# tc0xC_proto.net
KiCad netlist of a schematic drawn in EAGLE
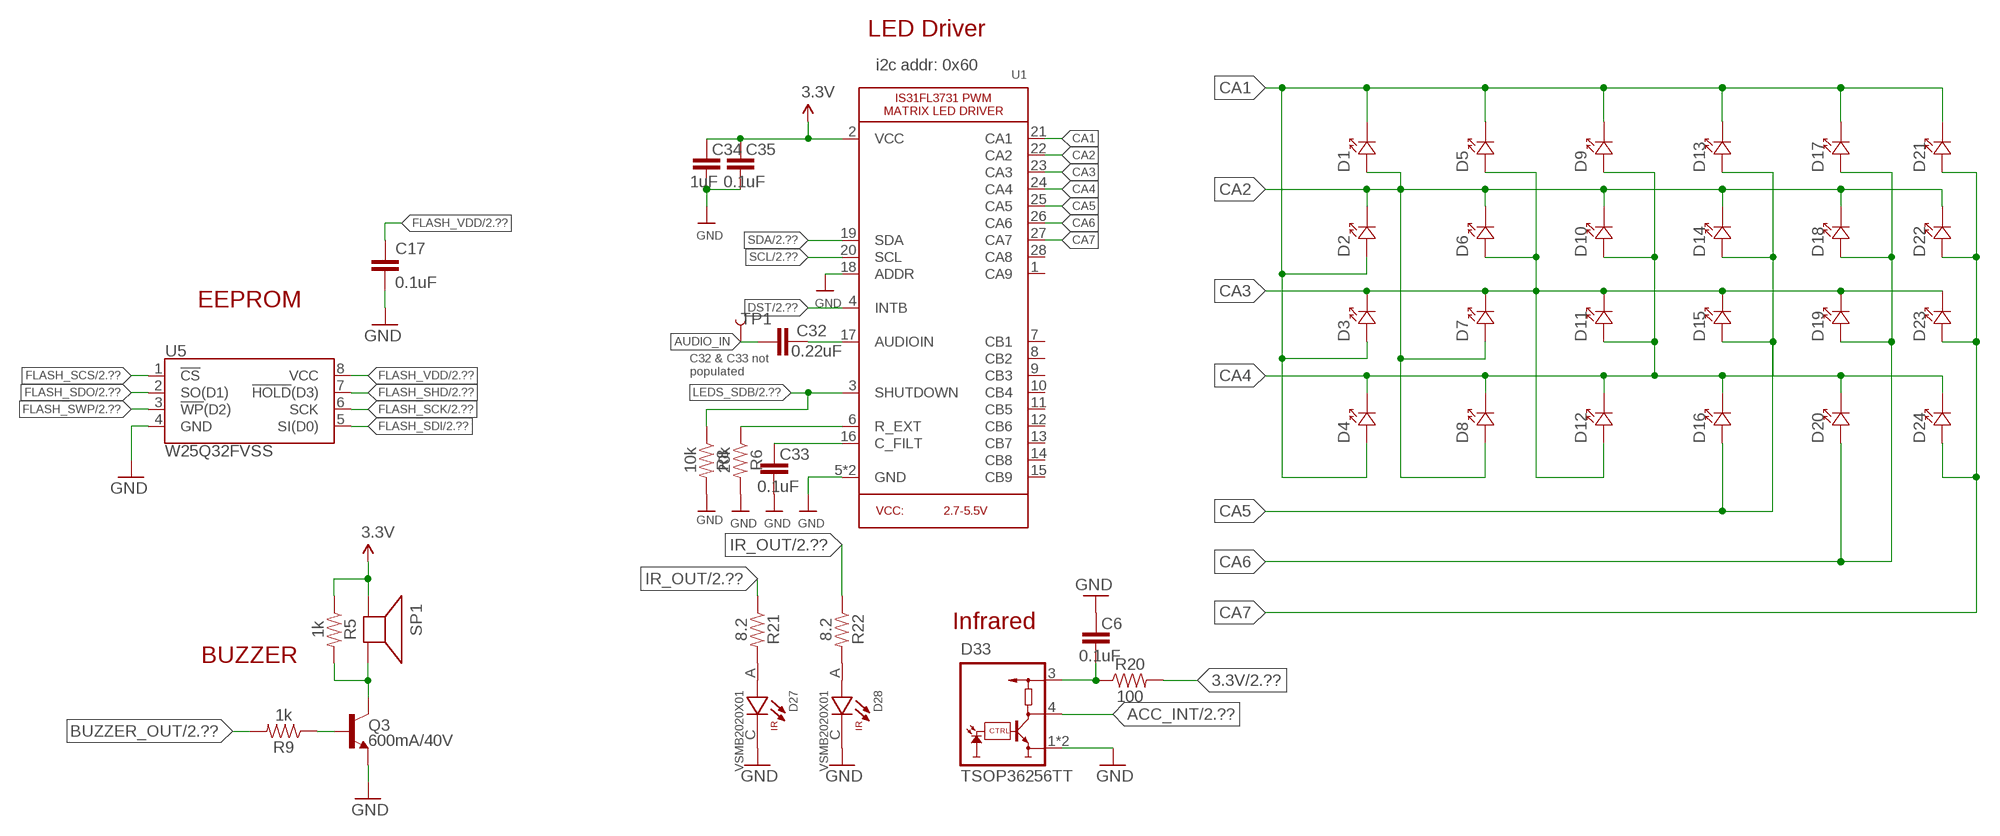
[diagram p0: schematic, sheet 1]
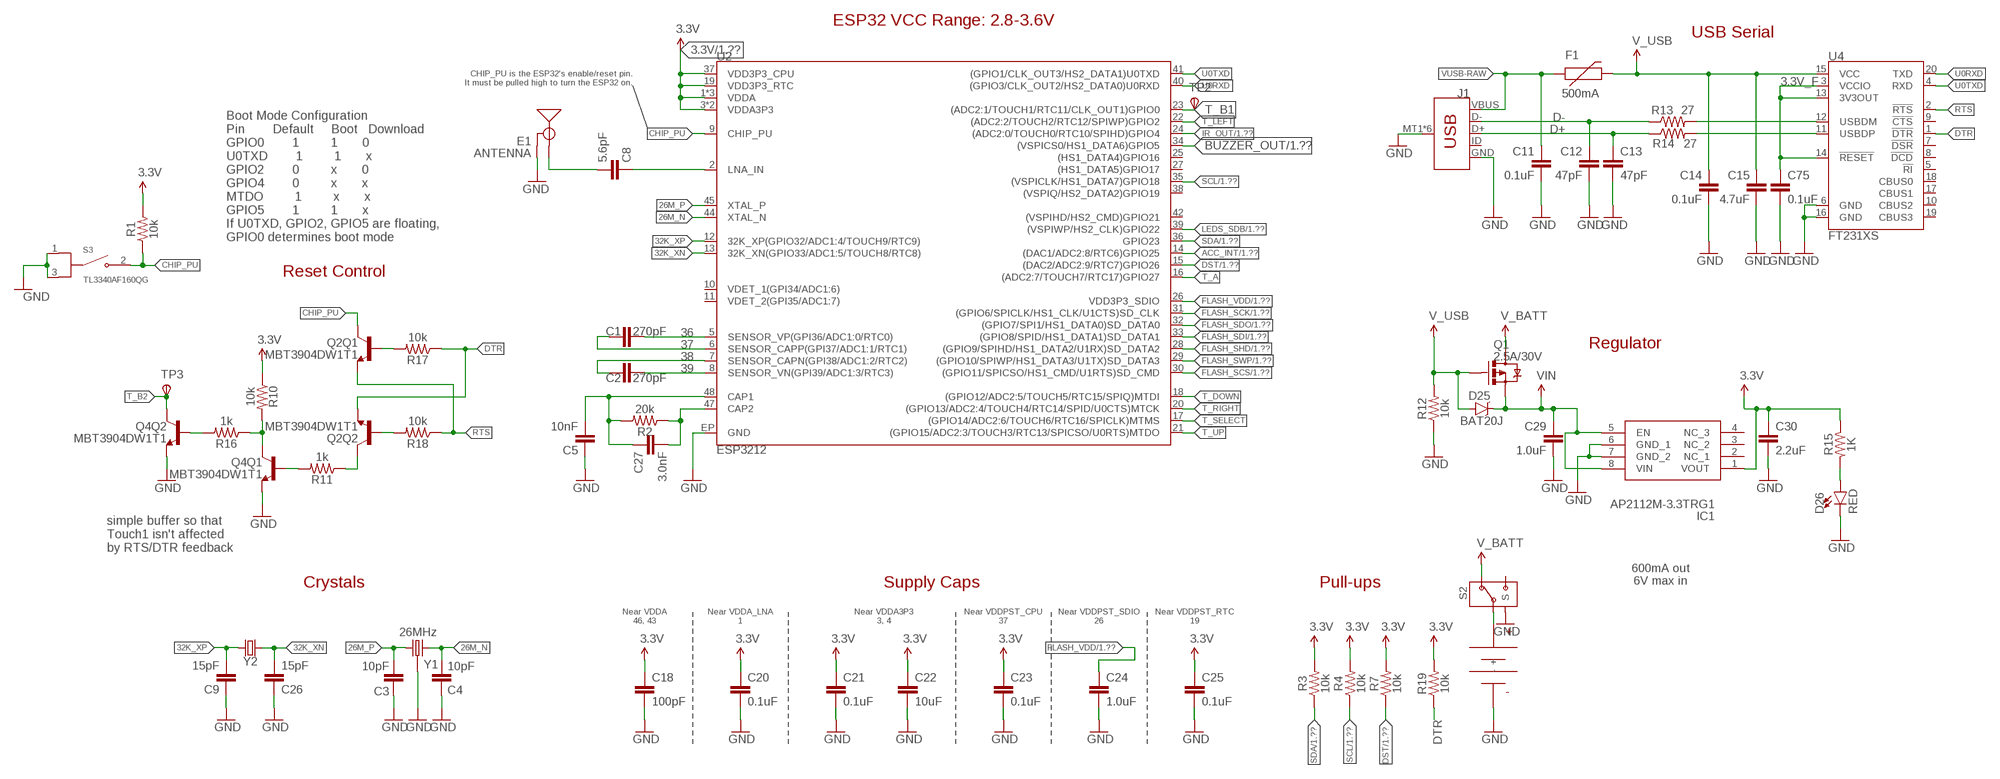
[diagram p1: schematic, sheet 2]

(export (version "E")
  (design (tool "Eeschema 10.0.6"))
  (components
    (comp (ref "C1")
      (value "270pF")
      (footprint "eagle-import:0603")
      (libsource (lib "eagle-import") (part "270PF-50V-5%(0603)"))
    )
    (comp (ref "C2")
      (value "270pF")
      (footprint "eagle-import:0603")
      (libsource (lib "eagle-import") (part "270PF-50V-5%(0603)"))
    )
    (comp (ref "C3")
      (value "10pF")
      (footprint "eagle-import:0603")
      (libsource (lib "eagle-import") (part "10PF-0603-50V-5%"))
    )
    (comp (ref "C4")
      (value "10pF")
      (footprint "eagle-import:0603")
      (libsource (lib "eagle-import") (part "10PF-0603-50V-5%"))
    )
    (comp (ref "C5")
      (value "10nF")
      (footprint "eagle-import:0603")
      (libsource (lib "eagle-import") (part "10NF-0603-50V-10%"))
    )
    (comp (ref "C8")
      (value "5.6pF")
      (footprint "eagle-import:0603")
      (libsource (lib "eagle-import") (part "5.6PF-50V-5%(0603)"))
    )
    (comp (ref "C9")
      (value "15pF")
      (footprint "eagle-import:0603")
      (libsource (lib "eagle-import") (part "15PF-0603-50V-5%"))
    )
    (comp (ref "C11")
      (value "0.1uF")
      (footprint "eagle-import:0603")
      (libsource (lib "eagle-import") (part "0.1UF-0603-25V-(+80/-20%)"))
    )
    (comp (ref "C12")
      (value "47pF")
      (footprint "eagle-import:0603")
      (libsource (lib "eagle-import") (part "47PF-0603-50V-5%"))
    )
    (comp (ref "C13")
      (value "47pF")
      (footprint "eagle-import:0603")
      (libsource (lib "eagle-import") (part "47PF-0603-50V-5%"))
    )
    (comp (ref "C14")
      (value "0.1uF")
      (footprint "eagle-import:0603")
      (libsource (lib "eagle-import") (part "0.1UF-0603-25V-(+80/-20%)"))
    )
    (comp (ref "C15")
      (value "4.7uF")
      (footprint "eagle-import:0603")
      (libsource (lib "eagle-import") (part "0.1UF-0603-25V-(+80/-20%)"))
    )
    (comp (ref "C18")
      (value "100pF")
      (footprint "eagle-import:0603")
      (libsource (lib "eagle-import") (part "100PF-0603-50V-5%"))
    )
    (comp (ref "C20")
      (value "0.1uF")
      (footprint "eagle-import:0603")
      (libsource (lib "eagle-import") (part "0.1UF-0603-25V-(+80/-20%)"))
    )
    (comp (ref "C21")
      (value "0.1uF")
      (footprint "eagle-import:0603")
      (libsource (lib "eagle-import") (part "0.1UF-0603-25V-(+80/-20%)"))
    )
    (comp (ref "C22")
      (value "10uF")
      (footprint "eagle-import:0603")
      (libsource (lib "eagle-import") (part "10UF-0603-6.3V-20%"))
    )
    (comp (ref "C23")
      (value "0.1uF")
      (footprint "eagle-import:0603")
      (libsource (lib "eagle-import") (part "0.1UF-0603-25V-(+80/-20%)"))
    )
    (comp (ref "C24")
      (value "1.0uF")
      (footprint "eagle-import:0603")
      (libsource (lib "eagle-import") (part "1.0UF-0603-16V-10%"))
    )
    (comp (ref "C25")
      (value "0.1uF")
      (footprint "eagle-import:0603")
      (libsource (lib "eagle-import") (part "0.1UF-0603-25V-(+80/-20%)"))
    )
    (comp (ref "C26")
      (value "15pF")
      (footprint "eagle-import:0603")
      (libsource (lib "eagle-import") (part "15PF-0603-50V-5%"))
    )
    (comp (ref "C27")
      (value "3.0nF")
      (footprint "eagle-import:0603")
      (libsource (lib "eagle-import") (part "3.0NF-0603-50V-5%"))
    )
    (comp (ref "C29")
      (value "1.0uF")
      (footprint "eagle-import:0805")
      (libsource (lib "eagle-import") (part "1.0UF-0805-25V-(+80/-20%)"))
    )
    (comp (ref "C30")
      (value "2.2uF")
      (footprint "eagle-import:0603")
      (libsource (lib "eagle-import") (part "2.2UF-0603-10V-20%"))
    )
    (comp (ref "C75")
      (value "0.1uF")
      (footprint "eagle-import:0603")
      (libsource (lib "eagle-import") (part "0.1UF-0603-25V-(+80/-20%)"))
    )
    (comp (ref "D25")
      (value "BAT20J")
      (footprint "eagle-import:SOD-323")
      (libsource (lib "eagle-import") (part "DIODE-SCHOTTKY-BAT20J"))
    )
    (comp (ref "D26")
      (value "RED")
      (footprint "eagle-import:LED-0603@1")
      (libsource (lib "eagle-import") (part "LED-RED0603"))
    )
    (comp (ref "E1")
      (value "ANTENNA")
      (footprint "eagle-import:TRACE_ANTENNA_2.4GHZ_25.7MM_TUNED")
      (libsource (lib "eagle-import") (part "ANTENNATRACE-TUNED"))
    )
    (comp (ref "F1")
      (value "500mA")
      (footprint "eagle-import:PTC-1206")
      (libsource (lib "eagle-import") (part "PTCSMD"))
    )
    (comp (ref "G2")
      (value "KEYSTONE_2479")
      (footprint "eagle-import:KEYSTONE_2479")
      (libsource (lib "eagle-import") (part "KEYSTONE_2479"))
    )
    (comp (ref "IC1")
      (value "AP2112M-3.3TRG1")
      (footprint "eagle-import:SOIC127P600X170-8N")
      (fields (field (name "MOUSER_PART_NUMBER") "621-AP2112M-3.3TRG1"))
      (libsource (lib "eagle-import") (part "AP2112M-3.3TRG1"))
    )
    (comp (ref "J1")
      (value "USB_MICRO-B")
      (footprint "eagle-import:USB-MICROB-10118192")
      (libsource (lib "eagle-import") (part "USB_MICRO-B"))
    )
    (comp (ref "Q1")
      (value "2.5A/30V")
      (footprint "eagle-import:SOT23-3@1")
      (libsource (lib "eagle-import") (part "MOSFET-PCHANNELDMG2307L"))
    )
    (comp (ref "Q2")
      (value "MBT3904DW1T1")
      (footprint "eagle-import:SC70-6")
      (libsource (lib "eagle-import") (part "MBT3904DW1T1"))
    )
    (comp (ref "Q4")
      (value "MBT3904DW1T1")
      (footprint "eagle-import:SC70-6")
      (libsource (lib "eagle-import") (part "MBT3904DW1T1"))
    )
    (comp (ref "R1")
      (value "10k")
      (footprint "eagle-import:0603")
      (libsource (lib "eagle-import") (part "10KOHM-1/10W-1%(0603)0603"))
    )
    (comp (ref "R2")
      (value "20k")
      (footprint "eagle-import:0603")
      (libsource (lib "eagle-import") (part "20KOHM-0603-1/10W-1%"))
    )
    (comp (ref "R3")
      (value "10k")
      (footprint "eagle-import:0603")
      (libsource (lib "eagle-import") (part "10KOHM-0603-1/10W-1%"))
    )
    (comp (ref "R4")
      (value "10k")
      (footprint "eagle-import:0603")
      (libsource (lib "eagle-import") (part "10KOHM-0603-1/10W-1%"))
    )
    (comp (ref "R7")
      (value "10k")
      (footprint "eagle-import:0603")
      (libsource (lib "eagle-import") (part "10KOHM-0603-1/10W-1%"))
    )
    (comp (ref "R10")
      (value "10k")
      (footprint "eagle-import:0603")
      (libsource (lib "eagle-import") (part "10KOHM-0603-1/10W-1%"))
    )
    (comp (ref "R11")
      (value "1k")
      (footprint "eagle-import:0603")
      (libsource (lib "eagle-import") (part "10KOHM-0603-1/10W-1%"))
    )
    (comp (ref "R12")
      (value "10k")
      (footprint "eagle-import:0603")
      (libsource (lib "eagle-import") (part "10KOHM-0603-1/10W-1%"))
    )
    (comp (ref "R13")
      (value "27")
      (footprint "eagle-import:0603")
      (libsource (lib "eagle-import") (part "27OHM1/10W1%(0603)0603-RES"))
    )
    (comp (ref "R14")
      (value "27")
      (footprint "eagle-import:0603")
      (libsource (lib "eagle-import") (part "27OHM1/10W1%(0603)0603-RES"))
    )
    (comp (ref "R15")
      (value "1K")
      (footprint "eagle-import:0603")
      (libsource (lib "eagle-import") (part "1KOHM-1/10W-1%(0603)"))
    )
    (comp (ref "R16")
      (value "1k")
      (footprint "eagle-import:0603")
      (libsource (lib "eagle-import") (part "10KOHM-0603-1/10W-1%"))
    )
    (comp (ref "R17")
      (value "10k")
      (footprint "eagle-import:0603")
      (libsource (lib "eagle-import") (part "10KOHM-0603-1/10W-1%"))
    )
    (comp (ref "R18")
      (value "10k")
      (footprint "eagle-import:0603")
      (libsource (lib "eagle-import") (part "10KOHM-0603-1/10W-1%"))
    )
    (comp (ref "R19")
      (value "10k")
      (footprint "eagle-import:0603")
      (libsource (lib "eagle-import") (part "10KOHM-0603-1/10W-1%"))
    )
    (comp (ref "S2")
      (value "CUS-12B")
      (footprint "eagle-import:CUS-12_SPDT")
      (libsource (lib "eagle-import") (part "CUS-12B"))
    )
    (comp (ref "S3")
      (value "TL3340AF160QG")
      (footprint "eagle-import:SW_TL3340AF160QG")
      (fields (field (name "MF") "E-Switch"))
      (libsource (lib "eagle-import") (part "TL3340AF160QG"))
    )
    (comp (ref "TP2")
      (value "TPSTP08R")
      (footprint "eagle-import:TP08R")
      (libsource (lib "eagle-import") (part "TPSTP08R"))
    )
    (comp (ref "TP3")
      (value "TPSTP08R")
      (footprint "eagle-import:TP08R")
      (libsource (lib "eagle-import") (part "TPSTP08R"))
    )
    (comp (ref "U2")
      (value "ESP3212")
      (footprint "eagle-import:QFN48-0.4MM")
      (libsource (lib "eagle-import") (part "ESP3212"))
    )
    (comp (ref "U4")
      (value "FT231XS")
      (footprint "eagle-import:SSOP20_L")
      (libsource (lib "eagle-import") (part "FT231XS"))
    )
    (comp (ref "Y1")
      (value "26MHz")
      (footprint "eagle-import:CRYSTAL-SMD-3.2X2.5")
      (libsource (lib "eagle-import") (part "CRYSTAL-GROUNDED3.2X2.5"))
    )
    (comp (ref "Y2")
      (value "32.768kHz")
      (footprint "eagle-import:FC-12M")
      (libsource (lib "eagle-import") (part "FC-12M"))
    )
    (comp (ref "C6")
      (value "0.1uF")
      (footprint "eagle-import:0603")
      (libsource (lib "eagle-import") (part "10PF-0603-50V-5%"))
    )
    (comp (ref "C17")
      (value "0.1uF")
      (footprint "eagle-import:0603")
      (libsource (lib "eagle-import") (part "0.1UF-0603-25V-(+80/-20%)"))
    )
    (comp (ref "C32")
      (value "0.22uF")
      (footprint "eagle-import:0603")
      (libsource (lib "eagle-import") (part "10PF-0603-50V-5%"))
    )
    (comp (ref "C33")
      (value "0.1uF")
      (footprint "eagle-import:0603")
      (libsource (lib "eagle-import") (part "10PF-0603-50V-5%"))
    )
    (comp (ref "C34")
      (value "1uF")
      (footprint "eagle-import:0603")
      (libsource (lib "eagle-import") (part "10PF-0603-50V-5%"))
    )
    (comp (ref "C35")
      (value "0.1uF")
      (footprint "eagle-import:0603")
      (libsource (lib "eagle-import") (part "10PF-0603-50V-5%"))
    )
    (comp (ref "D1")
      (value "LED-603")
      (footprint "eagle-import:SMD-603")
      (libsource (lib "eagle-import") (part "LED-603"))
    )
    (comp (ref "D2")
      (value "LED-603")
      (footprint "eagle-import:SMD-603")
      (libsource (lib "eagle-import") (part "LED-603"))
    )
    (comp (ref "D3")
      (value "LED-603")
      (footprint "eagle-import:SMD-603")
      (libsource (lib "eagle-import") (part "LED-603"))
    )
    (comp (ref "D4")
      (value "LED-603")
      (footprint "eagle-import:SMD-603")
      (libsource (lib "eagle-import") (part "LED-603"))
    )
    (comp (ref "D5")
      (value "LED-603")
      (footprint "eagle-import:SMD-603")
      (libsource (lib "eagle-import") (part "LED-603"))
    )
    (comp (ref "D6")
      (value "LED-603")
      (footprint "eagle-import:SMD-603")
      (libsource (lib "eagle-import") (part "LED-603"))
    )
    (comp (ref "D7")
      (value "LED-603")
      (footprint "eagle-import:SMD-603")
      (libsource (lib "eagle-import") (part "LED-603"))
    )
    (comp (ref "D8")
      (value "LED-603")
      (footprint "eagle-import:SMD-603")
      (libsource (lib "eagle-import") (part "LED-603"))
    )
    (comp (ref "D9")
      (value "LED-603")
      (footprint "eagle-import:SMD-603")
      (libsource (lib "eagle-import") (part "LED-603"))
    )
    (comp (ref "D10")
      (value "LED-603")
      (footprint "eagle-import:SMD-603")
      (libsource (lib "eagle-import") (part "LED-603"))
    )
    (comp (ref "D11")
      (value "LED-603")
      (footprint "eagle-import:SMD-603")
      (libsource (lib "eagle-import") (part "LED-603"))
    )
    (comp (ref "D12")
      (value "LED-603")
      (footprint "eagle-import:SMD-603")
      (libsource (lib "eagle-import") (part "LED-603"))
    )
    (comp (ref "D13")
      (value "LED-603")
      (footprint "eagle-import:SMD-603")
      (libsource (lib "eagle-import") (part "LED-603"))
    )
    (comp (ref "D14")
      (value "LED-603")
      (footprint "eagle-import:SMD-603")
      (libsource (lib "eagle-import") (part "LED-603"))
    )
    (comp (ref "D15")
      (value "LED-603")
      (footprint "eagle-import:SMD-603")
      (libsource (lib "eagle-import") (part "LED-603"))
    )
    (comp (ref "D16")
      (value "LED-603")
      (footprint "eagle-import:SMD-603")
      (libsource (lib "eagle-import") (part "LED-603"))
    )
    (comp (ref "D17")
      (value "LED-603")
      (footprint "eagle-import:SMD-603")
      (libsource (lib "eagle-import") (part "LED-603"))
    )
    (comp (ref "D18")
      (value "LED-603")
      (footprint "eagle-import:SMD-603")
      (libsource (lib "eagle-import") (part "LED-603"))
    )
    (comp (ref "D19")
      (value "LED-603")
      (footprint "eagle-import:SMD-603")
      (libsource (lib "eagle-import") (part "LED-603"))
    )
    (comp (ref "D20")
      (value "LED-603")
      (footprint "eagle-import:SMD-603")
      (libsource (lib "eagle-import") (part "LED-603"))
    )
    (comp (ref "D21")
      (value "LED-603")
      (footprint "eagle-import:SMD-603")
      (libsource (lib "eagle-import") (part "LED-603"))
    )
    (comp (ref "D22")
      (value "LED-603")
      (footprint "eagle-import:SMD-603")
      (libsource (lib "eagle-import") (part "LED-603"))
    )
    (comp (ref "D23")
      (value "LED-603")
      (footprint "eagle-import:SMD-603")
      (libsource (lib "eagle-import") (part "LED-603"))
    )
    (comp (ref "D24")
      (value "LED-603")
      (footprint "eagle-import:SMD-603")
      (libsource (lib "eagle-import") (part "LED-603"))
    )
    (comp (ref "D27")
      (value "VSMB2020X01")
      (footprint "eagle-import:DIO_VSMB2020X01")
      (fields (field (name "MF") "Vishay Semiconductors"))
      (libsource (lib "eagle-import") (part "VSMB2020X01"))
    )
    (comp (ref "D28")
      (value "VSMB2020X01")
      (footprint "eagle-import:DIO_VSMB2020X01")
      (fields (field (name "MF") "Vishay Semiconductors"))
      (libsource (lib "eagle-import") (part "VSMB2020X01"))
    )
    (comp (ref "D33")
      (value "TSOP36256TT")
      (footprint "eagle-import:TSOP36256")
      (fields (field (name "MF") "Vishay Semiconductors") (field (name "MP") "TSOP36256"))
      (libsource (lib "eagle-import") (part "TSOP36256TT"))
    )
    (comp (ref "Q3")
      (value "600mA/40V")
      (footprint "eagle-import:SOT23-3")
      (libsource (lib "eagle-import") (part "TRANS_NPN-MMBT2222AL"))
    )
    (comp (ref "R5")
      (value "1k")
      (footprint "eagle-import:0603")
      (libsource (lib "eagle-import") (part "10KOHM-0603-1/10W-1%"))
    )
    (comp (ref "R6")
      (value "20k")
      (footprint "eagle-import:0603")
      (libsource (lib "eagle-import") (part "10KOHM-0603-1/10W-1%"))
    )
    (comp (ref "R8")
      (value "10k")
      (footprint "eagle-import:0603")
      (libsource (lib "eagle-import") (part "10KOHM-0603-1/10W-1%"))
    )
    (comp (ref "R9")
      (value "1k")
      (footprint "eagle-import:0603")
      (libsource (lib "eagle-import") (part "10KOHM-0603-1/10W-1%"))
    )
    (comp (ref "R20")
      (value "100")
      (footprint "eagle-import:0603")
      (libsource (lib "eagle-import") (part "10KOHM-0603-1/10W-1%"))
    )
    (comp (ref "R21")
      (value "8.2")
      (footprint "eagle-import:0603")
      (libsource (lib "eagle-import") (part "10KOHM-0603-1/10W-1%"))
    )
    (comp (ref "R22")
      (value "8.2")
      (footprint "eagle-import:0603")
      (libsource (lib "eagle-import") (part "10KOHM-0603-1/10W-1%"))
    )
    (comp (ref "SP1")
      (value "SPEAKER/PS12")
      (footprint "eagle-import:PS12")
      (libsource (lib "eagle-import") (part "SPEAKER/PS12"))
    )
    (comp (ref "TP1")
      (value "TEST-POINT3X5")
      (footprint "eagle-import:PAD.03X.05")
      (libsource (lib "eagle-import") (part "TEST-POINT3X5"))
    )
    (comp (ref "U1")
      (value "IS31FL3731QFN")
      (footprint "eagle-import:QFN-28_4MM_0.4MM")
      (libsource (lib "eagle-import") (part "IS31FL3731QFN"))
    )
    (comp (ref "U5")
      (value "W25Q32FVSS")
      (footprint "eagle-import:SOIC-8")
      (libsource (lib "eagle-import") (part "W25Q32FVSS"))
    )
  )
  (nets
    (net (code "1") (name "3.3V") (class "Default")
      (node (ref "C18") (pin "1") (pinfunction "1_1") (pintype "passive"))
      (node (ref "C20") (pin "1") (pinfunction "1_1") (pintype "passive"))
      (node (ref "C21") (pin "1") (pinfunction "1_1") (pintype "passive"))
      (node (ref "C22") (pin "1") (pinfunction "1_1") (pintype "passive"))
      (node (ref "C23") (pin "1") (pinfunction "1_1") (pintype "passive"))
      (node (ref "C25") (pin "1") (pinfunction "1_1") (pintype "passive"))
      (node (ref "C30") (pin "1") (pinfunction "1_1") (pintype "passive"))
      (node (ref "C34") (pin "1") (pinfunction "1_1") (pintype "passive"))
      (node (ref "C35") (pin "1") (pinfunction "1_1") (pintype "passive"))
      (node (ref "C6") (pin "2") (pinfunction "2_2") (pintype "passive"))
      (node (ref "D33") (pin "3") (pinfunction "VS_3") (pintype "power_in"))
      (node (ref "IC1") (pin "1") (pinfunction "VOUT_1") (pintype "bidirectional"))
      (node (ref "R1") (pin "2") (pinfunction "2_2") (pintype "passive"))
      (node (ref "R10") (pin "1") (pinfunction "1_1") (pintype "passive"))
      (node (ref "R15") (pin "1") (pinfunction "1_1") (pintype "passive"))
      (node (ref "R19") (pin "2") (pinfunction "2_2") (pintype "passive"))
      (node (ref "R20") (pin "1") (pinfunction "1_1") (pintype "passive"))
      (node (ref "R20") (pin "2") (pinfunction "2_2") (pintype "passive"))
      (node (ref "R3") (pin "2") (pinfunction "2_2") (pintype "passive"))
      (node (ref "R4") (pin "2") (pinfunction "2_2") (pintype "passive"))
      (node (ref "R5") (pin "1") (pinfunction "1_1") (pintype "passive"))
      (node (ref "R7") (pin "2") (pinfunction "2_2") (pintype "passive"))
      (node (ref "SP1") (pin "P$1") (pinfunction "+_P$1") (pintype "passive"))
      (node (ref "U1") (pin "2") (pinfunction "VCC_2") (pintype "power_in"))
      (node (ref "U2") (pin "1") (pinfunction "VDDA_1") (pintype "bidirectional"))
      (node (ref "U2") (pin "19") (pinfunction "VDD3P3_RTC_19") (pintype "bidirectional"))
      (node (ref "U2") (pin "3") (pinfunction "VDDA3P3_3") (pintype "bidirectional"))
      (node (ref "U2") (pin "37") (pinfunction "VDD3P3_CPU_37") (pintype "bidirectional"))
      (node (ref "U2") (pin "4") (pinfunction "VDDA3P3_4") (pintype "bidirectional"))
      (node (ref "U2") (pin "43") (pinfunction "VDDA_43") (pintype "bidirectional"))
      (node (ref "U2") (pin "46") (pinfunction "VDDA_46") (pintype "bidirectional"))
    )
    (net (code "2") (name "3.3V_F") (class "Default")
      (node (ref "C75") (pin "1") (pinfunction "1_1") (pintype "passive"))
      (node (ref "U4") (pin "13") (pinfunction "3V3OUT_13") (pintype "bidirectional"))
      (node (ref "U4") (pin "14") (pinfunction "~{RESET}_14") (pintype "bidirectional"))
      (node (ref "U4") (pin "3") (pinfunction "VCCIO_3") (pintype "bidirectional"))
    )
    (net (code "3") (name "26M_N") (class "Default")
      (node (ref "C4") (pin "2") (pinfunction "2_2") (pintype "passive"))
      (node (ref "U2") (pin "44") (pinfunction "XTAL_N_44") (pintype "bidirectional"))
      (node (ref "Y1") (pin "3") (pinfunction "2_3") (pintype "passive"))
    )
    (net (code "4") (name "26M_P") (class "Default")
      (node (ref "C3") (pin "2") (pinfunction "2_2") (pintype "passive"))
      (node (ref "U2") (pin "45") (pinfunction "XTAL_P_45") (pintype "bidirectional"))
      (node (ref "Y1") (pin "1") (pinfunction "1_1") (pintype "passive"))
    )
    (net (code "5") (name "32K_XN") (class "Default")
      (node (ref "C26") (pin "2") (pinfunction "2_2") (pintype "passive"))
      (node (ref "U2") (pin "13") (pinfunction "32K_XN(GPIO33/ADC1:5/TOUCH8/RTC8)_13") (pintype "bidirectional"))
      (node (ref "Y2") (pin "2") (pinfunction "2_2") (pintype "passive"))
    )
    (net (code "6") (name "32K_XP") (class "Default")
      (node (ref "C9") (pin "2") (pinfunction "2_2") (pintype "passive"))
      (node (ref "U2") (pin "12") (pinfunction "32K_XP(GPIO32/ADC1:4/TOUCH9/RTC9)_12") (pintype "bidirectional"))
      (node (ref "Y2") (pin "1") (pinfunction "1_1") (pintype "passive"))
    )
    (net (code "7") (name "36") (class "Default")
      (node (ref "C1") (pin "2") (pinfunction "2_2") (pintype "passive"))
      (node (ref "U2") (pin "5") (pinfunction "SENSOR_VP(GPI36/ADC1:0/RTC0)_5") (pintype "bidirectional"))
    )
    (net (code "8") (name "37") (class "Default")
      (node (ref "C1") (pin "1") (pinfunction "1_1") (pintype "passive"))
      (node (ref "U2") (pin "6") (pinfunction "SENSOR_CAPP(GPI37/ADC1:1/RTC1)_6") (pintype "bidirectional"))
    )
    (net (code "9") (name "38") (class "Default")
      (node (ref "C2") (pin "1") (pinfunction "1_1") (pintype "passive"))
      (node (ref "U2") (pin "7") (pinfunction "SENSOR_CAPN(GPI38/ADC1:2/RTC2)_7") (pintype "bidirectional"))
    )
    (net (code "10") (name "39") (class "Default")
      (node (ref "C2") (pin "2") (pinfunction "2_2") (pintype "passive"))
      (node (ref "U2") (pin "8") (pinfunction "SENSOR_VN(GPI39/ADC1:3/RTC3)_8") (pintype "bidirectional"))
    )
    (net (code "11") (name "ACC_INT") (class "Default")
      (node (ref "D33") (pin "4") (pinfunction "OUT_4") (pintype "output"))
      (node (ref "U2") (pin "14") (pinfunction "(DAC1/ADC2:8/RTC6)GPIO25_14") (pintype "bidirectional"))
    )
    (net (code "12") (name "AUDIO_IN") (class "Default")
      (node (ref "C32") (pin "1") (pinfunction "1_1") (pintype "passive"))
      (node (ref "TP1") (pin "P$1") (pinfunction "1_P$1") (pintype "bidirectional"))
    )
    (net (code "13") (name "BUZZER_OUT") (class "Default")
      (node (ref "R9") (pin "2") (pinfunction "2_2") (pintype "passive"))
      (node (ref "U2") (pin "34") (pinfunction "(VSPICS0/HS1_DATA6)GPIO5_34") (pintype "bidirectional"))
    )
    (net (code "14") (name "CA1") (class "Default")
      (node (ref "D1") (pin "P$2") (pinfunction "CATHODE-_P$2") (pintype "bidirectional"))
      (node (ref "D13") (pin "P$2") (pinfunction "CATHODE-_P$2") (pintype "bidirectional"))
      (node (ref "D17") (pin "P$2") (pinfunction "CATHODE-_P$2") (pintype "bidirectional"))
      (node (ref "D2") (pin "P$1") (pinfunction "ANODE+_P$1") (pintype "bidirectional"))
      (node (ref "D21") (pin "P$2") (pinfunction "CATHODE-_P$2") (pintype "bidirectional"))
      (node (ref "D3") (pin "P$1") (pinfunction "ANODE+_P$1") (pintype "bidirectional"))
      (node (ref "D4") (pin "P$1") (pinfunction "ANODE+_P$1") (pintype "bidirectional"))
      (node (ref "D5") (pin "P$2") (pinfunction "CATHODE-_P$2") (pintype "bidirectional"))
      (node (ref "D9") (pin "P$2") (pinfunction "CATHODE-_P$2") (pintype "bidirectional"))
      (node (ref "U1") (pin "21") (pinfunction "CA1_21") (pintype "bidirectional"))
    )
    (net (code "15") (name "CA2") (class "Default")
      (node (ref "D1") (pin "P$1") (pinfunction "ANODE+_P$1") (pintype "bidirectional"))
      (node (ref "D10") (pin "P$2") (pinfunction "CATHODE-_P$2") (pintype "bidirectional"))
      (node (ref "D14") (pin "P$2") (pinfunction "CATHODE-_P$2") (pintype "bidirectional"))
      (node (ref "D18") (pin "P$2") (pinfunction "CATHODE-_P$2") (pintype "bidirectional"))
      (node (ref "D2") (pin "P$2") (pinfunction "CATHODE-_P$2") (pintype "bidirectional"))
      (node (ref "D22") (pin "P$2") (pinfunction "CATHODE-_P$2") (pintype "bidirectional"))
      (node (ref "D6") (pin "P$2") (pinfunction "CATHODE-_P$2") (pintype "bidirectional"))
      (node (ref "D7") (pin "P$1") (pinfunction "ANODE+_P$1") (pintype "bidirectional"))
      (node (ref "D8") (pin "P$1") (pinfunction "ANODE+_P$1") (pintype "bidirectional"))
      (node (ref "U1") (pin "22") (pinfunction "CA2_22") (pintype "bidirectional"))
    )
    (net (code "16") (name "CA3") (class "Default")
      (node (ref "D11") (pin "P$2") (pinfunction "CATHODE-_P$2") (pintype "bidirectional"))
      (node (ref "D12") (pin "P$1") (pinfunction "ANODE+_P$1") (pintype "bidirectional"))
      (node (ref "D15") (pin "P$2") (pinfunction "CATHODE-_P$2") (pintype "bidirectional"))
      (node (ref "D19") (pin "P$2") (pinfunction "CATHODE-_P$2") (pintype "bidirectional"))
      (node (ref "D23") (pin "P$2") (pinfunction "CATHODE-_P$2") (pintype "bidirectional"))
      (node (ref "D3") (pin "P$2") (pinfunction "CATHODE-_P$2") (pintype "bidirectional"))
      (node (ref "D5") (pin "P$1") (pinfunction "ANODE+_P$1") (pintype "bidirectional"))
      (node (ref "D6") (pin "P$1") (pinfunction "ANODE+_P$1") (pintype "bidirectional"))
      (node (ref "D7") (pin "P$2") (pinfunction "CATHODE-_P$2") (pintype "bidirectional"))
      (node (ref "U1") (pin "23") (pinfunction "CA3_23") (pintype "bidirectional"))
    )
    (net (code "17") (name "CA4") (class "Default")
      (node (ref "D10") (pin "P$1") (pinfunction "ANODE+_P$1") (pintype "bidirectional"))
      (node (ref "D11") (pin "P$1") (pinfunction "ANODE+_P$1") (pintype "bidirectional"))
      (node (ref "D12") (pin "P$2") (pinfunction "CATHODE-_P$2") (pintype "bidirectional"))
      (node (ref "D16") (pin "P$2") (pinfunction "CATHODE-_P$2") (pintype "bidirectional"))
      (node (ref "D20") (pin "P$2") (pinfunction "CATHODE-_P$2") (pintype "bidirectional"))
      (node (ref "D24") (pin "P$2") (pinfunction "CATHODE-_P$2") (pintype "bidirectional"))
      (node (ref "D4") (pin "P$2") (pinfunction "CATHODE-_P$2") (pintype "bidirectional"))
      (node (ref "D8") (pin "P$2") (pinfunction "CATHODE-_P$2") (pintype "bidirectional"))
      (node (ref "D9") (pin "P$1") (pinfunction "ANODE+_P$1") (pintype "bidirectional"))
      (node (ref "U1") (pin "24") (pinfunction "CA4_24") (pintype "bidirectional"))
    )
    (net (code "18") (name "CA5") (class "Default")
      (node (ref "D13") (pin "P$1") (pinfunction "ANODE+_P$1") (pintype "bidirectional"))
      (node (ref "D14") (pin "P$1") (pinfunction "ANODE+_P$1") (pintype "bidirectional"))
      (node (ref "D15") (pin "P$1") (pinfunction "ANODE+_P$1") (pintype "bidirectional"))
      (node (ref "D16") (pin "P$1") (pinfunction "ANODE+_P$1") (pintype "bidirectional"))
      (node (ref "U1") (pin "25") (pinfunction "CA5_25") (pintype "bidirectional"))
    )
    (net (code "19") (name "CA6") (class "Default")
      (node (ref "D17") (pin "P$1") (pinfunction "ANODE+_P$1") (pintype "bidirectional"))
      (node (ref "D18") (pin "P$1") (pinfunction "ANODE+_P$1") (pintype "bidirectional"))
      (node (ref "D19") (pin "P$1") (pinfunction "ANODE+_P$1") (pintype "bidirectional"))
      (node (ref "D20") (pin "P$1") (pinfunction "ANODE+_P$1") (pintype "bidirectional"))
      (node (ref "U1") (pin "26") (pinfunction "CA6_26") (pintype "bidirectional"))
    )
    (net (code "20") (name "CA7") (class "Default")
      (node (ref "D21") (pin "P$1") (pinfunction "ANODE+_P$1") (pintype "bidirectional"))
      (node (ref "D22") (pin "P$1") (pinfunction "ANODE+_P$1") (pintype "bidirectional"))
      (node (ref "D23") (pin "P$1") (pinfunction "ANODE+_P$1") (pintype "bidirectional"))
      (node (ref "D24") (pin "P$1") (pinfunction "ANODE+_P$1") (pintype "bidirectional"))
      (node (ref "U1") (pin "27") (pinfunction "CA7_27") (pintype "bidirectional"))
    )
    (net (code "21") (name "CHIP_PU") (class "Default")
      (node (ref "Q2") (pin "3") (pinfunction "C_3") (pintype "passive"))
      (node (ref "R1") (pin "1") (pinfunction "1_1") (pintype "passive"))
      (node (ref "S3") (pin "2") (pinfunction "NO_2") (pintype "passive"))
      (node (ref "U2") (pin "9") (pinfunction "CHIP_PU_9") (pintype "bidirectional"))
    )
    (net (code "22") (name "D+") (class "Default")
      (node (ref "C13") (pin "1") (pinfunction "1_1") (pintype "passive"))
      (node (ref "J1") (pin "D+") (pinfunction "D+_D+") (pintype "bidirectional"))
      (node (ref "R14") (pin "1") (pinfunction "1_1") (pintype "passive"))
    )
    (net (code "23") (name "D-") (class "Default")
      (node (ref "C12") (pin "1") (pinfunction "1_1") (pintype "passive"))
      (node (ref "J1") (pin "D-") (pinfunction "D-_D-") (pintype "bidirectional"))
      (node (ref "R13") (pin "1") (pinfunction "1_1") (pintype "passive"))
    )
    (net (code "24") (name "DST") (class "Default")
      (node (ref "R7") (pin "1") (pinfunction "1_1") (pintype "passive"))
      (node (ref "U1") (pin "4") (pinfunction "INTB_4") (pintype "output"))
      (node (ref "U2") (pin "15") (pinfunction "(DAC2/ADC2:9/RTC7)GPIO26_15") (pintype "bidirectional"))
    )
    (net (code "25") (name "DTR") (class "Default")
      (node (ref "Q2") (pin "1") (pinfunction "E_1") (pintype "passive"))
      (node (ref "R17") (pin "1") (pinfunction "1_1") (pintype "passive"))
      (node (ref "R19") (pin "1") (pinfunction "1_1") (pintype "passive"))
      (node (ref "U4") (pin "1") (pinfunction "~{DTR}_1") (pintype "bidirectional"))
    )
    (net (code "26") (name "FLASH_SCK") (class "Default")
      (node (ref "U2") (pin "31") (pinfunction "(GPIO6/SPICLK/HS1_CLK/U1CTS)SD_CLK_31") (pintype "bidirectional"))
      (node (ref "U5") (pin "6") (pinfunction "SCK_6") (pintype "bidirectional"))
    )
    (net (code "27") (name "FLASH_SCS") (class "Default")
      (node (ref "U2") (pin "30") (pinfunction "(GPIO11/SPICSO/HS1_CMD/U1RTS)SD_CMD_30") (pintype "bidirectional"))
      (node (ref "U5") (pin "1") (pinfunction "~{CS}_1") (pintype "bidirectional"))
    )
    (net (code "28") (name "FLASH_SDI") (class "Default")
      (node (ref "U2") (pin "33") (pinfunction "(GPIO8/SPID/HS1_DATA1)SD_DATA1_33") (pintype "bidirectional"))
      (node (ref "U5") (pin "5") (pinfunction "SI(D0)_5") (pintype "bidirectional"))
    )
    (net (code "29") (name "FLASH_SDO") (class "Default")
      (node (ref "U2") (pin "32") (pinfunction "(GPIO7/SPI1/HS1_DATA0)SD_DATA0_32") (pintype "bidirectional"))
      (node (ref "U5") (pin "2") (pinfunction "SO(D1)_2") (pintype "bidirectional"))
    )
    (net (code "30") (name "FLASH_SHD") (class "Default")
      (node (ref "U2") (pin "28") (pinfunction "(GPIO9/SPIHD/HS1_DATA2/U1RX)SD_DATA2_28") (pintype "bidirectional"))
      (node (ref "U5") (pin "7") (pinfunction "~{HOLD}(D3)_7") (pintype "bidirectional"))
    )
    (net (code "31") (name "FLASH_SWP") (class "Default")
      (node (ref "U2") (pin "29") (pinfunction "(GPIO10/SPIWP/HS1_DATA3/U1TX)SD_DATA3_29") (pintype "bidirectional"))
      (node (ref "U5") (pin "3") (pinfunction "~{WP}(D2)_3") (pintype "bidirectional"))
    )
    (net (code "32") (name "FLASH_VDD") (class "Default")
      (node (ref "C17") (pin "1") (pinfunction "1_1") (pintype "passive"))
      (node (ref "C24") (pin "1") (pinfunction "1_1") (pintype "passive"))
      (node (ref "U2") (pin "26") (pinfunction "VDD3P3_SDIO_26") (pintype "bidirectional"))
      (node (ref "U5") (pin "8") (pinfunction "VCC_8") (pintype "bidirectional"))
    )
    (net (code "33") (name "GND") (class "Default")
      (node (ref "C11") (pin "2") (pinfunction "2_2") (pintype "passive"))
      (node (ref "C12") (pin "2") (pinfunction "2_2") (pintype "passive"))
      (node (ref "C13") (pin "2") (pinfunction "2_2") (pintype "passive"))
      (node (ref "C14") (pin "2") (pinfunction "2_2") (pintype "passive"))
      (node (ref "C15") (pin "2") (pinfunction "2_2") (pintype "passive"))
      (node (ref "C17") (pin "2") (pinfunction "2_2") (pintype "passive"))
      (node (ref "C18") (pin "2") (pinfunction "2_2") (pintype "passive"))
      (node (ref "C20") (pin "2") (pinfunction "2_2") (pintype "passive"))
      (node (ref "C21") (pin "2") (pinfunction "2_2") (pintype "passive"))
      (node (ref "C22") (pin "2") (pinfunction "2_2") (pintype "passive"))
      (node (ref "C23") (pin "2") (pinfunction "2_2") (pintype "passive"))
      (node (ref "C24") (pin "2") (pinfunction "2_2") (pintype "passive"))
      (node (ref "C25") (pin "2") (pinfunction "2_2") (pintype "passive"))
      (node (ref "C26") (pin "1") (pinfunction "1_1") (pintype "passive"))
      (node (ref "C29") (pin "2") (pinfunction "2_2") (pintype "passive"))
      (node (ref "C3") (pin "1") (pinfunction "1_1") (pintype "passive"))
      (node (ref "C30") (pin "2") (pinfunction "2_2") (pintype "passive"))
      (node (ref "C33") (pin "2") (pinfunction "2_2") (pintype "passive"))
      (node (ref "C34") (pin "2") (pinfunction "2_2") (pintype "passive"))
      (node (ref "C35") (pin "2") (pinfunction "2_2") (pintype "passive"))
      (node (ref "C4") (pin "1") (pinfunction "1_1") (pintype "passive"))
      (node (ref "C5") (pin "1") (pinfunction "1_1") (pintype "passive"))
      (node (ref "C6") (pin "1") (pinfunction "1_1") (pintype "passive"))
      (node (ref "C75") (pin "2") (pinfunction "2_2") (pintype "passive"))
      (node (ref "C9") (pin "1") (pinfunction "1_1") (pintype "passive"))
      (node (ref "D26") (pin "C") (pinfunction "C_C") (pintype "passive"))
      (node (ref "D27") (pin "C") (pinfunction "C_C") (pintype "passive"))
      (node (ref "D28") (pin "C") (pinfunction "C_C") (pintype "passive"))
      (node (ref "D33") (pin "1") (pinfunction "GND_1") (pintype "power_in"))
      (node (ref "D33") (pin "2") (pinfunction "GND_2") (pintype "power_in"))
      (node (ref "E1") (pin "GND") (pinfunction "GND_GND") (pintype "bidirectional"))
      (node (ref "E1") (pin "GND2") (pinfunction "GND_GND2") (pintype "bidirectional"))
      (node (ref "G2") (pin "-") (pinfunction "-_-") (pintype "bidirectional"))
      (node (ref "IC1") (pin "6") (pinfunction "GND_1_6") (pintype "bidirectional"))
      (node (ref "IC1") (pin "7") (pinfunction "GND_2_7") (pintype "bidirectional"))
      (node (ref "J1") (pin "GND") (pinfunction "GND_GND") (pintype "power_in"))
      (node (ref "J1") (pin "MT1") (pinfunction "SHIELD_MT1") (pintype "bidirectional"))
      (node (ref "J1") (pin "MT2") (pinfunction "SHIELD_MT2") (pintype "bidirectional"))
      (node (ref "J1") (pin "MT3") (pinfunction "SHIELD_MT3") (pintype "bidirectional"))
      (node (ref "J1") (pin "MT4") (pinfunction "SHIELD_MT4") (pintype "bidirectional"))
      (node (ref "J1") (pin "P$1") (pinfunction "SHIELD_P$1") (pintype "bidirectional"))
      (node (ref "J1") (pin "P$2") (pinfunction "SHIELD_P$2") (pintype "bidirectional"))
      (node (ref "Q3") (pin "2") (pinfunction "E_2") (pintype "passive"))
      (node (ref "Q4") (pin "1") (pinfunction "E_1") (pintype "passive"))
      (node (ref "Q4") (pin "4") (pinfunction "E_4") (pintype "passive"))
      (node (ref "R12") (pin "1") (pinfunction "1_1") (pintype "passive"))
      (node (ref "R6") (pin "2") (pinfunction "2_2") (pintype "passive"))
      (node (ref "R8") (pin "2") (pinfunction "2_2") (pintype "passive"))
      (node (ref "S2") (pin "P$4") (pinfunction "S_P$4") (pintype "bidirectional"))
      (node (ref "S2") (pin "P$5") (pinfunction "S_P$5") (pintype "bidirectional"))
      (node (ref "S2") (pin "P$6") (pinfunction "S_P$6") (pintype "bidirectional"))
      (node (ref "S2") (pin "P$7") (pinfunction "S_P$7") (pintype "bidirectional"))
      (node (ref "S3") (pin "1") (pinfunction "COM_1_1") (pintype "passive"))
      (node (ref "S3") (pin "3") (pinfunction "COM_2_3") (pintype "passive"))
      (node (ref "U1") (pin "18") (pinfunction "ADDR_18") (pintype "bidirectional"))
      (node (ref "U1") (pin "5") (pinfunction "GND_5") (pintype "power_in"))
      (node (ref "U1") (pin "THERMAL") (pinfunction "GND_THERMAL") (pintype "power_in"))
      (node (ref "U2") (pin "EP") (pinfunction "GND_EP") (pintype "bidirectional"))
      (node (ref "U4") (pin "16") (pinfunction "GND_16") (pintype "bidirectional"))
      (node (ref "U4") (pin "6") (pinfunction "GND_6") (pintype "bidirectional"))
      (node (ref "U5") (pin "4") (pinfunction "GND_4") (pintype "bidirectional"))
      (node (ref "Y1") (pin "2") (pinfunction "GND_2") (pintype "passive"))
      (node (ref "Y1") (pin "4") (pinfunction "GND_4") (pintype "passive"))
    )
    (net (code "34") (name "IR_OUT") (class "Default")
      (node (ref "R21") (pin "1") (pinfunction "1_1") (pintype "passive"))
      (node (ref "R22") (pin "1") (pinfunction "1_1") (pintype "passive"))
      (node (ref "U2") (pin "24") (pinfunction "(ADC2:0/TOUCH0/RTC10/SPIHD)GPIO4_24") (pintype "bidirectional"))
    )
    (net (code "35") (name "LEDS_SDB") (class "Default")
      (node (ref "R8") (pin "1") (pinfunction "1_1") (pintype "passive"))
      (node (ref "U1") (pin "3") (pinfunction "SHUTDOWN_3") (pintype "input"))
      (node (ref "U2") (pin "39") (pinfunction "(VSPIWP/HS2_CLK)GPIO22_39") (pintype "bidirectional"))
    )
    (net (code "36") (name "Net-(D26-PadA)") (class "Default")
      (node (ref "D26") (pin "A") (pinfunction "A_A") (pintype "passive"))
      (node (ref "R15") (pin "2") (pinfunction "2_2") (pintype "passive"))
    )
    (net (code "37") (name "Net-(D27-PadA)") (class "Default")
      (node (ref "D27") (pin "A") (pinfunction "A_A") (pintype "passive"))
      (node (ref "R21") (pin "2") (pinfunction "2_2") (pintype "passive"))
    )
    (net (code "38") (name "Net-(D28-PadA)") (class "Default")
      (node (ref "D28") (pin "A") (pinfunction "A_A") (pintype "passive"))
      (node (ref "R22") (pin "2") (pinfunction "2_2") (pintype "passive"))
    )
    (net (code "39") (name "Net-(E1-SIGNAL)") (class "Default")
      (node (ref "C8") (pin "2") (pinfunction "2_2") (pintype "passive"))
      (node (ref "E1") (pin "ANT") (pinfunction "SIGNAL_ANT") (pintype "bidirectional"))
    )
    (net (code "40") (name "Net-(Q2A-B)") (class "Default")
      (node (ref "Q2") (pin "5") (pinfunction "B_5") (pintype "passive"))
      (node (ref "R17") (pin "2") (pinfunction "2_2") (pintype "passive"))
    )
    (net (code "41") (name "Net-(Q2B-B)") (class "Default")
      (node (ref "Q2") (pin "2") (pinfunction "B_2") (pintype "passive"))
      (node (ref "R18") (pin "2") (pinfunction "2_2") (pintype "passive"))
    )
    (net (code "42") (name "Net-(Q2B-C)") (class "Default")
      (node (ref "Q2") (pin "6") (pinfunction "C_6") (pintype "passive"))
      (node (ref "R11") (pin "1") (pinfunction "1_1") (pintype "passive"))
    )
    (net (code "43") (name "Net-(Q3-B)") (class "Default")
      (node (ref "Q3") (pin "1") (pinfunction "B_1") (pintype "passive"))
      (node (ref "R9") (pin "1") (pinfunction "1_1") (pintype "passive"))
    )
    (net (code "44") (name "Net-(Q3-C)") (class "Default")
      (node (ref "Q3") (pin "3") (pinfunction "C_3") (pintype "passive"))
      (node (ref "R5") (pin "2") (pinfunction "2_2") (pintype "passive"))
      (node (ref "SP1") (pin "P$2") (pinfunction "-_P$2") (pintype "passive"))
    )
    (net (code "45") (name "Net-(Q4A-B)") (class "Default")
      (node (ref "Q4") (pin "5") (pinfunction "B_5") (pintype "passive"))
      (node (ref "R11") (pin "2") (pinfunction "2_2") (pintype "passive"))
    )
    (net (code "46") (name "Net-(Q4A-C)") (class "Default")
      (node (ref "Q4") (pin "3") (pinfunction "C_3") (pintype "passive"))
      (node (ref "R10") (pin "2") (pinfunction "2_2") (pintype "passive"))
      (node (ref "R16") (pin "1") (pinfunction "1_1") (pintype "passive"))
    )
    (net (code "47") (name "Net-(Q4B-B)") (class "Default")
      (node (ref "Q4") (pin "2") (pinfunction "B_2") (pintype "passive"))
      (node (ref "R16") (pin "2") (pinfunction "2_2") (pintype "passive"))
    )
    (net (code "48") (name "Net-(S2-1)") (class "Default")
      (node (ref "G2") (pin "+") (pinfunction "+_+") (pintype "bidirectional"))
      (node (ref "S2") (pin "P$2") (pinfunction "1_P$2") (pintype "bidirectional"))
    )
    (net (code "49") (name "Net-(U1-AUDIOIN)") (class "Default")
      (node (ref "C32") (pin "2") (pinfunction "2_2") (pintype "passive"))
      (node (ref "U1") (pin "17") (pinfunction "AUDIOIN_17") (pintype "input"))
    )
    (net (code "50") (name "Net-(U1-C_FILT)") (class "Default")
      (node (ref "C33") (pin "1") (pinfunction "1_1") (pintype "passive"))
      (node (ref "U1") (pin "16") (pinfunction "C_FILT_16") (pintype "bidirectional"))
    )
    (net (code "51") (name "Net-(U1-R_EXT)") (class "Default")
      (node (ref "R6") (pin "1") (pinfunction "1_1") (pintype "passive"))
      (node (ref "U1") (pin "6") (pinfunction "R_EXT_6") (pintype "bidirectional"))
    )
    (net (code "52") (name "Net-(U2-CAP1)") (class "Default")
      (node (ref "C27") (pin "1") (pinfunction "1_1") (pintype "passive"))
      (node (ref "C5") (pin "2") (pinfunction "2_2") (pintype "passive"))
      (node (ref "R2") (pin "2") (pinfunction "2_2") (pintype "passive"))
      (node (ref "U2") (pin "48") (pinfunction "CAP1_48") (pintype "bidirectional"))
    )
    (net (code "53") (name "Net-(U2-CAP2)") (class "Default")
      (node (ref "C27") (pin "2") (pinfunction "2_2") (pintype "passive"))
      (node (ref "R2") (pin "1") (pinfunction "1_1") (pintype "passive"))
      (node (ref "U2") (pin "47") (pinfunction "CAP2_47") (pintype "bidirectional"))
    )
    (net (code "54") (name "Net-(U2-LNA_IN)") (class "Default")
      (node (ref "C8") (pin "1") (pinfunction "1_1") (pintype "passive"))
      (node (ref "U2") (pin "2") (pinfunction "LNA_IN_2") (pintype "bidirectional"))
    )
    (net (code "55") (name "Net-(U4-USBDM)") (class "Default")
      (node (ref "R13") (pin "2") (pinfunction "2_2") (pintype "passive"))
      (node (ref "U4") (pin "12") (pinfunction "USBDM_12") (pintype "bidirectional"))
    )
    (net (code "56") (name "Net-(U4-USBDP)") (class "Default")
      (node (ref "R14") (pin "2") (pinfunction "2_2") (pintype "passive"))
      (node (ref "U4") (pin "11") (pinfunction "USBDP_11") (pintype "bidirectional"))
    )
    (net (code "57") (name "RTS") (class "Default")
      (node (ref "Q2") (pin "4") (pinfunction "E_4") (pintype "passive"))
      (node (ref "R18") (pin "1") (pinfunction "1_1") (pintype "passive"))
      (node (ref "U4") (pin "2") (pinfunction "~{RTS}_2") (pintype "bidirectional"))
    )
    (net (code "58") (name "SCL") (class "Default")
      (node (ref "R4") (pin "1") (pinfunction "1_1") (pintype "passive"))
      (node (ref "U1") (pin "20") (pinfunction "SCL_20") (pintype "bidirectional"))
      (node (ref "U2") (pin "35") (pinfunction "(VSPICLK/HS1_DATA7)GPIO18_35") (pintype "bidirectional"))
    )
    (net (code "59") (name "SDA") (class "Default")
      (node (ref "R3") (pin "1") (pinfunction "1_1") (pintype "passive"))
      (node (ref "U1") (pin "19") (pinfunction "SDA_19") (pintype "bidirectional"))
      (node (ref "U2") (pin "36") (pinfunction "GPIO23_36") (pintype "bidirectional"))
    )
    (net (code "60") (name "T_A") (class "Default")
      (node (ref "U2") (pin "16") (pinfunction "(ADC2:7/TOUCH7/RTC17)GPIO27_16") (pintype "bidirectional"))
    )
    (net (code "61") (name "T_B1") (class "Default")
      (node (ref "TP2") (pin "TP") (pinfunction "PP_TP") (pintype "input"))
      (node (ref "U2") (pin "23") (pinfunction "(ADC2:1/TOUCH1/RTC11/CLK_OUT1)GPIO0_23") (pintype "bidirectional"))
    )
    (net (code "62") (name "T_B2") (class "Default")
      (node (ref "Q4") (pin "6") (pinfunction "C_6") (pintype "passive"))
      (node (ref "TP3") (pin "TP") (pinfunction "PP_TP") (pintype "input"))
    )
    (net (code "63") (name "T_DOWN") (class "Default")
      (node (ref "U2") (pin "18") (pinfunction "(GPIO12/ADC2:5/TOUCH5/RTC15/SPIQ)MTDI_18") (pintype "bidirectional"))
    )
    (net (code "64") (name "T_LEFT") (class "Default")
      (node (ref "U2") (pin "22") (pinfunction "(ADC2:2/TOUCH2/RTC12/SPIWP)GPIO2_22") (pintype "bidirectional"))
    )
    (net (code "65") (name "T_RIGHT") (class "Default")
      (node (ref "U2") (pin "20") (pinfunction "(GPIO13/ADC2:4/TOUCH4/RTC14/SPID/U0CTS)MTCK_20") (pintype "bidirectional"))
    )
    (net (code "66") (name "T_SELECT") (class "Default")
      (node (ref "U2") (pin "17") (pinfunction "(GPIO14/ADC2:6/TOUCH6/RTC16/SPICLK)MTMS_17") (pintype "bidirectional"))
    )
    (net (code "67") (name "T_UP") (class "Default")
      (node (ref "U2") (pin "21") (pinfunction "(GPIO15/ADC2:3/TOUCH3/RTC13/SPICSO/U0RTS)MTDO_21") (pintype "bidirectional"))
    )
    (net (code "68") (name "U0RXD") (class "Default")
      (node (ref "U2") (pin "40") (pinfunction "(GPIO3/CLK_OUT2/HS2_DATA0)U0RXD_40") (pintype "bidirectional"))
      (node (ref "U4") (pin "20") (pinfunction "TXD_20") (pintype "bidirectional"))
    )
    (net (code "69") (name "U0TXD") (class "Default")
      (node (ref "U2") (pin "41") (pinfunction "(GPIO1/CLK_OUT3/HS2_DATA1)U0TXD_41") (pintype "bidirectional"))
      (node (ref "U4") (pin "4") (pinfunction "RXD_4") (pintype "bidirectional"))
    )
    (net (code "70") (name "VIN") (class "Default")
      (node (ref "C29") (pin "1") (pinfunction "1_1") (pintype "passive"))
      (node (ref "D25") (pin "C") (pinfunction "C_C") (pintype "passive"))
      (node (ref "IC1") (pin "5") (pinfunction "EN_5") (pintype "bidirectional"))
      (node (ref "IC1") (pin "8") (pinfunction "VIN_8") (pintype "bidirectional"))
      (node (ref "Q1") (pin "2") (pinfunction "S_2") (pintype "passive"))
    )
    (net (code "71") (name "VUSB-RAW") (class "Default")
      (node (ref "C11") (pin "1") (pinfunction "1_1") (pintype "passive"))
      (node (ref "F1") (pin "1") (pinfunction "1_1") (pintype "bidirectional"))
      (node (ref "J1") (pin "VBUS") (pinfunction "VBUS_VBUS") (pintype "power_in"))
    )
    (net (code "72") (name "V_BATT") (class "Default")
      (node (ref "Q1") (pin "3") (pinfunction "D_3") (pintype "passive"))
      (node (ref "S2") (pin "P$1") (pinfunction "2_P$1") (pintype "bidirectional"))
    )
    (net (code "73") (name "V_USB") (class "Default")
      (node (ref "C14") (pin "1") (pinfunction "1_1") (pintype "passive"))
      (node (ref "C15") (pin "1") (pinfunction "1_1") (pintype "passive"))
      (node (ref "D25") (pin "A") (pinfunction "A_A") (pintype "passive"))
      (node (ref "F1") (pin "2") (pinfunction "2_2") (pintype "bidirectional"))
      (node (ref "Q1") (pin "1") (pinfunction "G_1") (pintype "passive"))
      (node (ref "R12") (pin "2") (pinfunction "2_2") (pintype "passive"))
      (node (ref "U4") (pin "15") (pinfunction "VCC_15") (pintype "bidirectional"))
    )
    (net (code "74") (name "unconnected-(IC1-NC_1-Pad2)") (class "Default")
      (node (ref "IC1") (pin "2") (pinfunction "NC_1_2") (pintype "bidirectional"))
    )
    (net (code "75") (name "unconnected-(IC1-NC_2-Pad3)") (class "Default")
      (node (ref "IC1") (pin "3") (pinfunction "NC_2_3") (pintype "bidirectional"))
    )
    (net (code "76") (name "unconnected-(IC1-NC_3-Pad4)") (class "Default")
      (node (ref "IC1") (pin "4") (pinfunction "NC_3_4") (pintype "bidirectional"))
    )
    (net (code "77") (name "unconnected-(J1-PadID)") (class "Default")
      (node (ref "J1") (pin "ID") (pinfunction "ID_ID") (pintype "bidirectional"))
    )
    (net (code "78") (name "unconnected-(S2-3-PadP$3)") (class "Default")
      (node (ref "S2") (pin "P$3") (pinfunction "3_P$3") (pintype "bidirectional"))
    )
    (net (code "79") (name "unconnected-(U1-CA8-Pad28)") (class "Default")
      (node (ref "U1") (pin "28") (pinfunction "CA8_28") (pintype "bidirectional"))
    )
    (net (code "80") (name "unconnected-(U1-CA9-Pad1)") (class "Default")
      (node (ref "U1") (pin "1") (pinfunction "CA9_1") (pintype "bidirectional"))
    )
    (net (code "81") (name "unconnected-(U1-CB1-Pad7)") (class "Default")
      (node (ref "U1") (pin "7") (pinfunction "CB1_7") (pintype "bidirectional"))
    )
    (net (code "82") (name "unconnected-(U1-CB2-Pad8)") (class "Default")
      (node (ref "U1") (pin "8") (pinfunction "CB2_8") (pintype "bidirectional"))
    )
    (net (code "83") (name "unconnected-(U1-CB3-Pad9)") (class "Default")
      (node (ref "U1") (pin "9") (pinfunction "CB3_9") (pintype "bidirectional"))
    )
    (net (code "84") (name "unconnected-(U1-CB4-Pad10)") (class "Default")
      (node (ref "U1") (pin "10") (pinfunction "CB4_10") (pintype "bidirectional"))
    )
    (net (code "85") (name "unconnected-(U1-CB5-Pad11)") (class "Default")
      (node (ref "U1") (pin "11") (pinfunction "CB5_11") (pintype "bidirectional"))
    )
    (net (code "86") (name "unconnected-(U1-CB6-Pad12)") (class "Default")
      (node (ref "U1") (pin "12") (pinfunction "CB6_12") (pintype "bidirectional"))
    )
    (net (code "87") (name "unconnected-(U1-CB7-Pad13)") (class "Default")
      (node (ref "U1") (pin "13") (pinfunction "CB7_13") (pintype "bidirectional"))
    )
    (net (code "88") (name "unconnected-(U1-CB8-Pad14)") (class "Default")
      (node (ref "U1") (pin "14") (pinfunction "CB8_14") (pintype "bidirectional"))
    )
    (net (code "89") (name "unconnected-(U1-CB9-Pad15)") (class "Default")
      (node (ref "U1") (pin "15") (pinfunction "CB9_15") (pintype "bidirectional"))
    )
    (net (code "90") (name "unconnected-(U2-(HS1_DATA4)GPIO16-Pad25)") (class "Default")
      (node (ref "U2") (pin "25") (pinfunction "(HS1_DATA4)GPIO16_25") (pintype "bidirectional"))
    )
    (net (code "91") (name "unconnected-(U2-(HS1_DATA5)GPIO17-Pad27)") (class "Default")
      (node (ref "U2") (pin "27") (pinfunction "(HS1_DATA5)GPIO17_27") (pintype "bidirectional"))
    )
    (net (code "92") (name "unconnected-(U2-(VSPIHD{slash}HS2_CMD)GPIO21-Pad42)") (class "Default")
      (node (ref "U2") (pin "42") (pinfunction "(VSPIHD/HS2_CMD)GPIO21_42") (pintype "bidirectional"))
    )
    (net (code "93") (name "unconnected-(U2-(VSPIQ{slash}HS2_DATA2)GPIO19-Pad38)") (class "Default")
      (node (ref "U2") (pin "38") (pinfunction "(VSPIQ/HS2_DATA2)GPIO19_38") (pintype "bidirectional"))
    )
    (net (code "94") (name "unconnected-(U2-VDET_1(GPI34{slash}ADC1:6)-Pad10)") (class "Default")
      (node (ref "U2") (pin "10") (pinfunction "VDET_1(GPI34/ADC1:6)_10") (pintype "bidirectional"))
    )
    (net (code "95") (name "unconnected-(U2-VDET_2(GPI35{slash}ADC1:7)-Pad11)") (class "Default")
      (node (ref "U2") (pin "11") (pinfunction "VDET_2(GPI35/ADC1:7)_11") (pintype "bidirectional"))
    )
    (net (code "96") (name "unconnected-(U4-CBUS0-Pad18)") (class "Default")
      (node (ref "U4") (pin "18") (pinfunction "CBUS0_18") (pintype "bidirectional"))
    )
    (net (code "97") (name "unconnected-(U4-CBUS1-Pad17)") (class "Default")
      (node (ref "U4") (pin "17") (pinfunction "CBUS1_17") (pintype "bidirectional"))
    )
    (net (code "98") (name "unconnected-(U4-CBUS2-Pad10)") (class "Default")
      (node (ref "U4") (pin "10") (pinfunction "CBUS2_10") (pintype "bidirectional"))
    )
    (net (code "99") (name "unconnected-(U4-CBUS3-Pad19)") (class "Default")
      (node (ref "U4") (pin "19") (pinfunction "CBUS3_19") (pintype "bidirectional"))
    )
    (net (code "100") (name "unconnected-(U4-~{CTS}-Pad9)") (class "Default")
      (node (ref "U4") (pin "9") (pinfunction "~{CTS}_9") (pintype "bidirectional"))
    )
    (net (code "101") (name "unconnected-(U4-~{DCD}-Pad8)") (class "Default")
      (node (ref "U4") (pin "8") (pinfunction "~{DCD}_8") (pintype "bidirectional"))
    )
    (net (code "102") (name "unconnected-(U4-~{DSR}-Pad7)") (class "Default")
      (node (ref "U4") (pin "7") (pinfunction "~{DSR}_7") (pintype "bidirectional"))
    )
    (net (code "103") (name "unconnected-(U4-~{RI}-Pad5)") (class "Default")
      (node (ref "U4") (pin "5") (pinfunction "~{RI}_5") (pintype "bidirectional"))
    )
  )
)
